# TX_Board.net
KiCad netlist of a schematic drawn in EAGLE
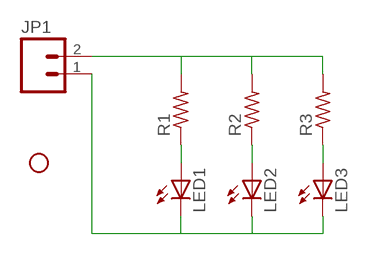
[diagram p0: schematic, sheet 1]

(export (version "E")
  (design (tool "Eeschema 10.0.6"))
  (components
    (comp (ref "JP1")
      (value "M02PTH4")
      (footprint "eagle-import:1X02_XTRA_BIG")
      (libsource (lib "eagle-import") (part "M02PTH4"))
    )
    (comp (ref "JP2")
      (value "STAND-OFF")
      (footprint "eagle-import:STAND-OFF")
      (libsource (lib "eagle-import") (part "STAND-OFF"))
    )
    (comp (ref "LED1")
      (value "LED-FKIT-1206")
      (footprint "eagle-import:FKIT-LED-1206")
      (libsource (lib "eagle-import") (part "LED-FKIT-1206"))
    )
    (comp (ref "LED2")
      (value "LED-FKIT-1206")
      (footprint "eagle-import:FKIT-LED-1206")
      (libsource (lib "eagle-import") (part "LED-FKIT-1206"))
    )
    (comp (ref "LED3")
      (value "LED-FKIT-1206")
      (footprint "eagle-import:FKIT-LED-1206")
      (libsource (lib "eagle-import") (part "LED-FKIT-1206"))
    )
    (comp (ref "R1")
      (value "R-US_M1206")
      (footprint "eagle-import:M1206")
      (libsource (lib "eagle-import") (part "R-US_M1206"))
    )
    (comp (ref "R2")
      (value "R-US_M1206")
      (footprint "eagle-import:M1206")
      (libsource (lib "eagle-import") (part "R-US_M1206"))
    )
    (comp (ref "R3")
      (value "R-US_M1206")
      (footprint "eagle-import:M1206")
      (libsource (lib "eagle-import") (part "R-US_M1206"))
    )
  )
  (nets
    (net (code "1") (name "Net-(JP1-Pad1)") (class "Default")
      (node (ref "JP1") (pin "1") (pinfunction "1_1") (pintype "passive"))
      (node (ref "LED1") (pin "C") (pinfunction "C_C") (pintype "passive"))
      (node (ref "LED2") (pin "C") (pinfunction "C_C") (pintype "passive"))
      (node (ref "LED3") (pin "C") (pinfunction "C_C") (pintype "passive"))
    )
    (net (code "2") (name "Net-(JP1-Pad2)") (class "Default")
      (node (ref "JP1") (pin "2") (pinfunction "2_2") (pintype "passive"))
      (node (ref "R1") (pin "2") (pinfunction "2_2") (pintype "passive"))
      (node (ref "R2") (pin "2") (pinfunction "2_2") (pintype "passive"))
      (node (ref "R3") (pin "2") (pinfunction "2_2") (pintype "passive"))
    )
    (net (code "3") (name "Net-(LED1-PadA)") (class "Default")
      (node (ref "LED1") (pin "A") (pinfunction "A_A") (pintype "passive"))
      (node (ref "R1") (pin "1") (pinfunction "1_1") (pintype "passive"))
    )
    (net (code "4") (name "Net-(LED2-PadA)") (class "Default")
      (node (ref "LED2") (pin "A") (pinfunction "A_A") (pintype "passive"))
      (node (ref "R2") (pin "1") (pinfunction "1_1") (pintype "passive"))
    )
    (net (code "5") (name "Net-(LED3-PadA)") (class "Default")
      (node (ref "LED3") (pin "A") (pinfunction "A_A") (pintype "passive"))
      (node (ref "R3") (pin "1") (pinfunction "1_1") (pintype "passive"))
    )
  )
)
